# SCH_junwoo-board_2025-07-26.net
KiCad netlist of a schematic drawn in EasyEDA
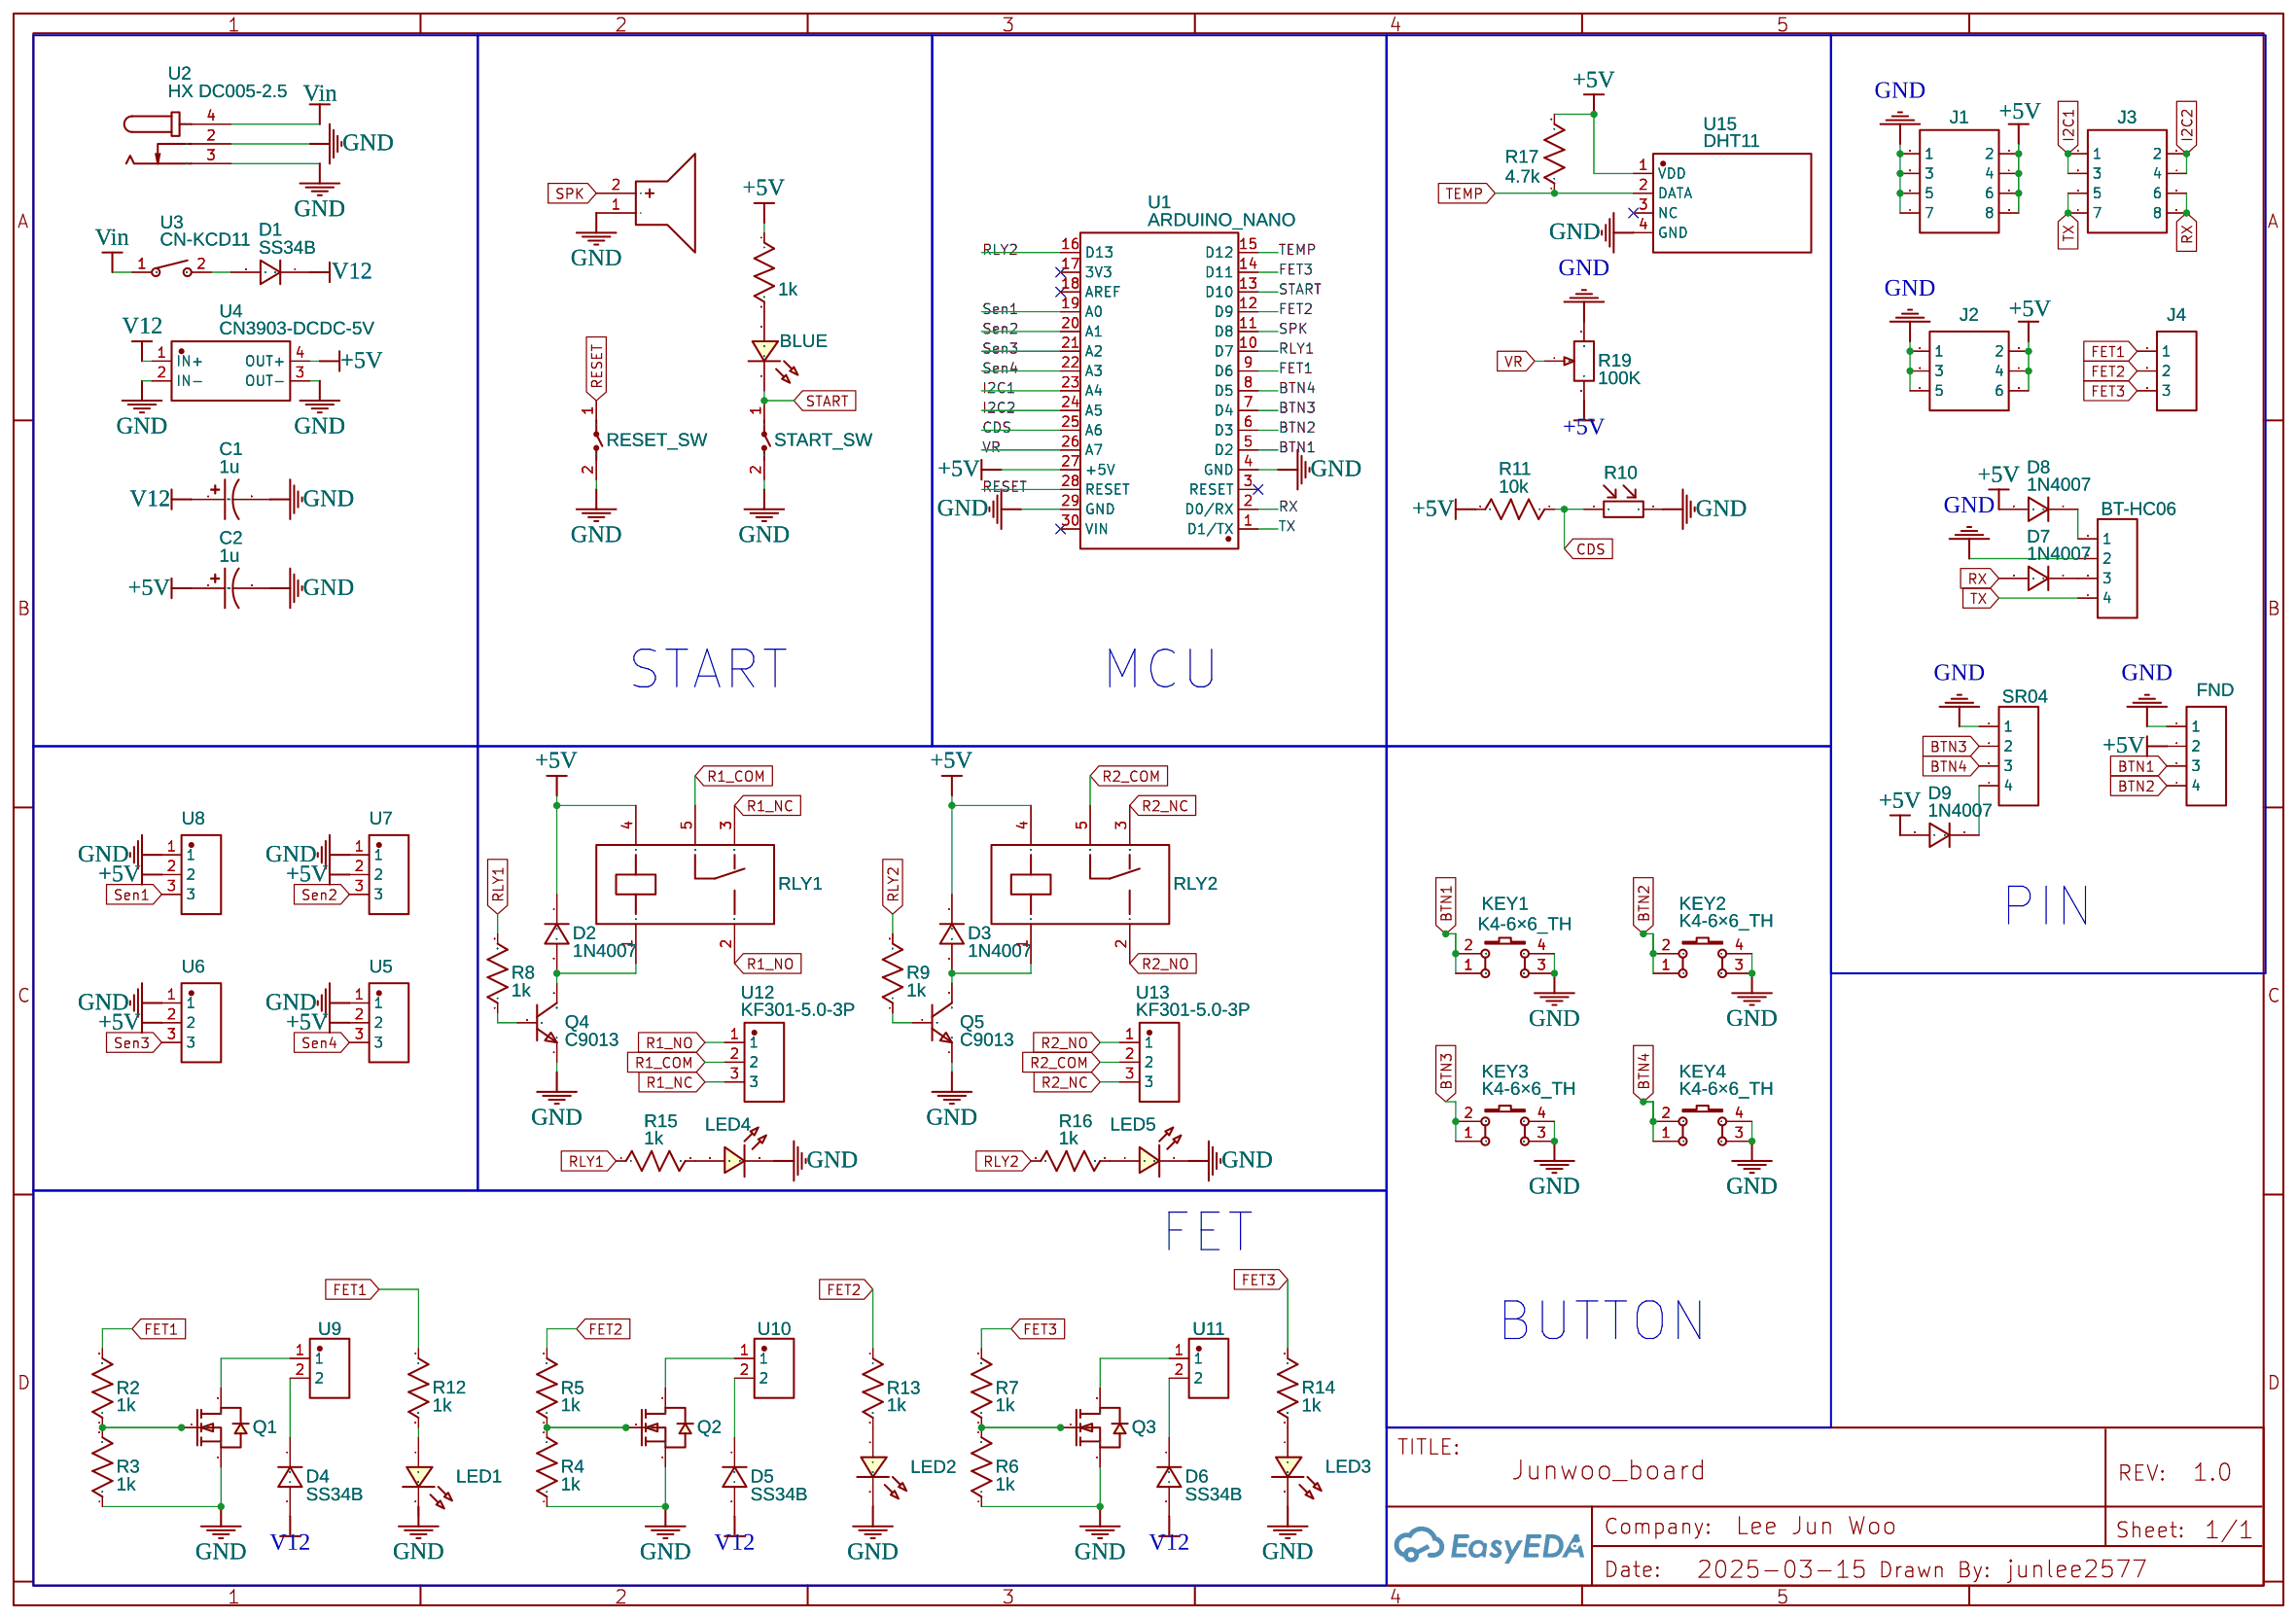
[diagram p0: schematic sheet]

(export (version "E")
  (design (tool "Eeschema 10.0.6"))
  (components
    (comp (ref "BLUE")
      (value "LED-TH-3mm_B")
      (fields
        (field (name "Manufacturer Part") "204-10SUBC/S400-A4")
        (field (name "Manufacturer") "EVERLIGHT(台湾亿光)")
      )
      (libsource (lib "") (part "LED-TH-3mm_B"))
    )
    (comp (ref "BT-HC06") (value "HDR-M-2.54_1x4") (libsource (lib "") (part "HDR-M-2.54_1x4_2")))
    (comp (ref "BUZZER1")
      (value "BUZZER")
      (fields (field (name "Manufacturer Part") "buzzer"))
      (libsource (lib "") (part "BUZZER"))
    )
    (comp (ref "C1") (value "1u") (libsource (lib "") (part "CE_TH_D6.3×F2.5_US")))
    (comp (ref "C2") (value "1u") (libsource (lib "") (part "CE_TH_D6.3×F2.5_US")))
    (comp (ref "D1")
      (value "SS34B")
      (fields (field (name "Manufacturer") "晶导微电子"))
      (libsource (lib "") (part "SS34B_1"))
    )
    (comp (ref "D2")
      (value "1N4007")
      (fields (field (name "Manufacturer") "SEMTECH"))
      (libsource (lib "") (part "1N4007_1"))
    )
    (comp (ref "D3")
      (value "1N4007")
      (fields (field (name "Manufacturer") "SEMTECH"))
      (libsource (lib "") (part "1N4007_1"))
    )
    (comp (ref "D4")
      (value "SS34B")
      (fields (field (name "Manufacturer") "晶导微电子"))
      (libsource (lib "") (part "SS34B"))
    )
    (comp (ref "D5")
      (value "SS34B")
      (fields (field (name "Manufacturer") "晶导微电子"))
      (libsource (lib "") (part "SS34B"))
    )
    (comp (ref "D6")
      (value "SS34B")
      (fields (field (name "Manufacturer") "晶导微电子"))
      (libsource (lib "") (part "SS34B"))
    )
    (comp (ref "D7")
      (value "1N4007")
      (fields (field (name "Manufacturer") "SEMTECH"))
      (libsource (lib "") (part "1N4007"))
    )
    (comp (ref "D8")
      (value "1N4007")
      (fields (field (name "Manufacturer") "SEMTECH"))
      (libsource (lib "") (part "1N4007"))
    )
    (comp (ref "D9")
      (value "1N4007")
      (fields (field (name "Manufacturer") "SEMTECH"))
      (libsource (lib "") (part "1N4007"))
    )
    (comp (ref "FND") (value "HDR-M-2.54_1x4") (libsource (lib "") (part "HDR-M-2.54_1x4")))
    (comp (ref "J1") (value "HDR-M-2.54_2x4") (libsource (lib "") (part "HDR-M-2.54_2x4")))
    (comp (ref "J2") (value "HDR-M-2.54_2x3") (libsource (lib "") (part "HDR-M-2.54_2x3")))
    (comp (ref "J3") (value "HDR-M-2.54_2x4") (libsource (lib "") (part "HDR-M-2.54_2x4")))
    (comp (ref "J4") (value "HDR-M-2.54_1x3") (libsource (lib "") (part "HDR-M-2.54_1x3")))
    (comp (ref "KEY1")
      (value "K4-6×6_TH")
      (fields (field (name "Manufacturer Part") "K2-1102DP-E4SW-04") (field (name "Manufacturer") "韩国韩荣"))
      (libsource (lib "") (part "K4-6×6_TH"))
    )
    (comp (ref "KEY2")
      (value "K4-6×6_TH")
      (fields (field (name "Manufacturer Part") "K2-1102DP-E4SW-04") (field (name "Manufacturer") "韩国韩荣"))
      (libsource (lib "") (part "K4-6×6_TH"))
    )
    (comp (ref "KEY3")
      (value "K4-6×6_TH")
      (fields (field (name "Manufacturer Part") "K2-1102DP-E4SW-04") (field (name "Manufacturer") "韩国韩荣"))
      (libsource (lib "") (part "K4-6×6_TH"))
    )
    (comp (ref "KEY4")
      (value "K4-6×6_TH")
      (fields (field (name "Manufacturer Part") "K2-1102DP-E4SW-04") (field (name "Manufacturer") "韩国韩荣"))
      (libsource (lib "") (part "K4-6×6_TH"))
    )
    (comp (ref "LED1") (value "LED-TH-5mm_B") (libsource (lib "") (part "LED-TH-5mm_B")))
    (comp (ref "LED2") (value "LED-TH-5mm_B") (libsource (lib "") (part "LED-TH-5mm_B")))
    (comp (ref "LED3") (value "LED-TH-5mm_B") (libsource (lib "") (part "LED-TH-5mm_B")))
    (comp (ref "LED4") (value "LED-TH-5mm_B") (libsource (lib "") (part "LED-TH-5mm_B_1")))
    (comp (ref "LED5") (value "LED-TH-5mm_B") (libsource (lib "") (part "LED-TH-5mm_B_1")))
    (comp (ref "Q1")
      (value "IRLZ44ZPBF")
      (fields (field (name "Manufacturer") "Infineon(英飞凌)"))
      (libsource (lib "") (part "IRLZ44ZPBF"))
    )
    (comp (ref "Q2")
      (value "IRLZ44ZPBF")
      (fields (field (name "Manufacturer") "Infineon(英飞凌)"))
      (libsource (lib "") (part "IRLZ44ZPBF"))
    )
    (comp (ref "Q3")
      (value "IRLZ44ZPBF")
      (fields (field (name "Manufacturer") "Infineon(英飞凌)"))
      (libsource (lib "") (part "IRLZ44ZPBF"))
    )
    (comp (ref "Q4") (value "C9013") (libsource (lib "") (part "C9013")))
    (comp (ref "Q5") (value "C9013") (libsource (lib "") (part "C9013")))
    (comp (ref "R1") (value "1k") (libsource (lib "") (part "R_AXIAL-0.4_US_2")))
    (comp (ref "R2") (value "1k") (libsource (lib "") (part "R_AXIAL-0.4_US_1")))
    (comp (ref "R3") (value "1k") (libsource (lib "") (part "R_AXIAL-0.4_US_1")))
    (comp (ref "R4") (value "1k") (libsource (lib "") (part "R_AXIAL-0.4_US_1")))
    (comp (ref "R5") (value "1k") (libsource (lib "") (part "R_AXIAL-0.4_US_1")))
    (comp (ref "R6") (value "1k") (libsource (lib "") (part "R_AXIAL-0.4_US_1")))
    (comp (ref "R7") (value "1k") (libsource (lib "") (part "R_AXIAL-0.4_US_1")))
    (comp (ref "R8") (value "1k") (libsource (lib "") (part "R_AXIAL-0.4_US_1")))
    (comp (ref "R9") (value "1k") (libsource (lib "") (part "R_AXIAL-0.4_US_1")))
    (comp (ref "R10")
      (value "GL5528(10-20)_C520869")
      (fields (field (name "Manufacturer Part") "GL5528(10-20)") (field (name "Manufacturer") "JCHL(晶创和立)"))
      (libsource (lib "") (part "GL5528(10-20)_C520869"))
    )
    (comp (ref "R11") (value "10k") (libsource (lib "") (part "R_AXIAL-0.4_US_3")))
    (comp (ref "R12") (value "1k") (libsource (lib "") (part "R_AXIAL-0.4_US_2")))
    (comp (ref "R13") (value "1k") (libsource (lib "") (part "R_AXIAL-0.4_US_2")))
    (comp (ref "R14") (value "1k") (libsource (lib "") (part "R_AXIAL-0.4_US_2")))
    (comp (ref "R15") (value "1k") (libsource (lib "") (part "R_AXIAL-0.4_US")))
    (comp (ref "R16") (value "1k") (libsource (lib "") (part "R_AXIAL-0.4_US")))
    (comp (ref "R17") (value "4.7k") (libsource (lib "") (part "R_AXIAL-0.4_US_1")))
    (comp (ref "R19")
      (value "100K")
      (fields
        (field (name "Manufacturer Part") "Potentiometer WH160-1-104")
        (field (name "Manufacturer") "JML")
      )
      (libsource (lib "") (part "RV09AF_schütze"))
    )
    (comp (ref "RESET_SW")
      (value "TS-1001-AR04326")
      (fields (field (name "Manufacturer") "XUNPU(讯普)"))
      (libsource (lib "") (part "TS-1001-AR04326_1"))
    )
    (comp (ref "RLY1")
      (value "5V-12V SRD05VDCSLC")
      (fields (field (name "Manufacturer Part") "SRD-05VDC-SL-C") (field (name "Manufacturer") "松乐"))
      (libsource (lib "") (part "SRD-05VDC-SL-C"))
    )
    (comp (ref "RLY2")
      (value "5V-12V SRD05VDCSLC")
      (fields (field (name "Manufacturer Part") "SRD-05VDC-SL-C") (field (name "Manufacturer") "松乐"))
      (libsource (lib "") (part "SRD-05VDC-SL-C"))
    )
    (comp (ref "SR04") (value "HDR-M-2.54_1x4") (libsource (lib "") (part "HDR-M-2.54_1x4_1")))
    (comp (ref "START_SW")
      (value "TS-1001-AR04326")
      (fields (field (name "Manufacturer") "XUNPU(讯普)"))
      (libsource (lib "") (part "TS-1001-AR04326"))
    )
    (comp (ref "U1") (value "ARDUINO_NANO") (libsource (lib "") (part "ARDUINO_NANO")))
    (comp (ref "U2")
      (value "HX DC005-2.5")
      (fields (field (name "Manufacturer") "hanxia(韩下)"))
      (libsource (lib "") (part "HX DC005-2.5"))
    )
    (comp (ref "U3") (value "CN-KCD11") (libsource (lib "") (part "CN-KCD11")))
    (comp (ref "U4") (value "CN3903-DCDC-5V") (libsource (lib "") (part "CN3903-DCDC-STEPDOWN-5V")))
    (comp (ref "U5")
      (value "KF350-3.5-3P")
      (fields (field (name "Manufacturer") "KEFA(科发)"))
      (libsource (lib "") (part "KF350-3.5-3P"))
    )
    (comp (ref "U6")
      (value "KF350-3.5-3P")
      (fields (field (name "Manufacturer") "KEFA(科发)"))
      (libsource (lib "") (part "KF350-3.5-3P"))
    )
    (comp (ref "U7")
      (value "KF350-3.5-3P")
      (fields (field (name "Manufacturer") "KEFA(科发)"))
      (libsource (lib "") (part "KF350-3.5-3P"))
    )
    (comp (ref "U8")
      (value "KF350-3.5-3P")
      (fields (field (name "Manufacturer") "KEFA(科发)"))
      (libsource (lib "") (part "KF350-3.5-3P"))
    )
    (comp (ref "U9")
      (value "KF301-5.0-2P")
      (fields (field (name "Manufacturer") "KEFA(科发)"))
      (libsource (lib "") (part "KF301-5.0-2P"))
    )
    (comp (ref "U10")
      (value "KF301-5.0-2P")
      (fields (field (name "Manufacturer") "KEFA(科发)"))
      (libsource (lib "") (part "KF301-5.0-2P"))
    )
    (comp (ref "U11")
      (value "KF301-5.0-2P")
      (fields (field (name "Manufacturer") "KEFA(科发)"))
      (libsource (lib "") (part "KF301-5.0-2P"))
    )
    (comp (ref "U12")
      (value "KF301-5.0-3P")
      (fields (field (name "Manufacturer") "KEFA(科发)"))
      (libsource (lib "") (part "KF301-5.0-3P"))
    )
    (comp (ref "U13")
      (value "KF301-5.0-3P")
      (fields (field (name "Manufacturer") "KEFA(科发)"))
      (libsource (lib "") (part "KF301-5.0-3P"))
    )
    (comp (ref "U15")
      (value "DHT11")
      (fields (field (name "Manufacturer") "广州奥松"))
      (libsource (lib "") (part "DHT11"))
    )
  )
  (nets
    (net (code "1") (name "+5V") (class "Default")
      (node (ref "C2") (pin "1") (pinfunction "1_1") (pintype "unspecified"))
      (node (ref "D2") (pin "1") (pinfunction "1_1") (pintype "unspecified"))
      (node (ref "D3") (pin "1") (pinfunction "1_1") (pintype "unspecified"))
      (node (ref "D8") (pin "2") (pinfunction "2_2") (pintype "unspecified"))
      (node (ref "D9") (pin "2") (pinfunction "2_2") (pintype "unspecified"))
      (node (ref "FND") (pin "2") (pinfunction "2_2") (pintype "unspecified"))
      (node (ref "J1") (pin "2") (pinfunction "2_2") (pintype "unspecified"))
      (node (ref "J1") (pin "4") (pinfunction "4_4") (pintype "unspecified"))
      (node (ref "J1") (pin "6") (pinfunction "6_6") (pintype "unspecified"))
      (node (ref "J1") (pin "8") (pinfunction "8_8") (pintype "unspecified"))
      (node (ref "J2") (pin "2") (pinfunction "2_2") (pintype "input"))
      (node (ref "J2") (pin "4") (pinfunction "4_4") (pintype "input"))
      (node (ref "J2") (pin "6") (pinfunction "6_6") (pintype "input"))
      (node (ref "R1") (pin "1") (pinfunction "1_1") (pintype "unspecified"))
      (node (ref "R11") (pin "2") (pinfunction "2_2") (pintype "unspecified"))
      (node (ref "R17") (pin "2") (pinfunction "2_2") (pintype "unspecified"))
      (node (ref "R19") (pin "3") (pinfunction "1_3") (pintype "input"))
      (node (ref "RLY1") (pin "4") (pinfunction "4_4") (pintype "unspecified"))
      (node (ref "RLY2") (pin "4") (pinfunction "4_4") (pintype "unspecified"))
      (node (ref "U1") (pin "27") (pinfunction "+5V_27") (pintype "unspecified"))
      (node (ref "U15") (pin "1") (pinfunction "VDD_1") (pintype "unspecified"))
      (node (ref "U4") (pin "4") (pinfunction "OUT+_4") (pintype "unspecified"))
      (node (ref "U5") (pin "2") (pinfunction "2_2") (pintype "unspecified"))
      (node (ref "U6") (pin "2") (pinfunction "2_2") (pintype "unspecified"))
      (node (ref "U7") (pin "2") (pinfunction "2_2") (pintype "unspecified"))
      (node (ref "U8") (pin "2") (pinfunction "2_2") (pintype "unspecified"))
    )
    (net (code "2") (name "BTN1") (class "Default")
      (node (ref "FND") (pin "3") (pinfunction "3_3") (pintype "unspecified"))
      (node (ref "KEY1") (pin "1") (pinfunction "1_1") (pintype "unspecified"))
      (node (ref "KEY1") (pin "2") (pinfunction "2_2") (pintype "unspecified"))
      (node (ref "U1") (pin "5") (pinfunction "D2_5") (pintype "unspecified"))
    )
    (net (code "3") (name "BTN2") (class "Default")
      (node (ref "FND") (pin "4") (pinfunction "4_4") (pintype "unspecified"))
      (node (ref "KEY2") (pin "1") (pinfunction "1_1") (pintype "unspecified"))
      (node (ref "KEY2") (pin "2") (pinfunction "2_2") (pintype "unspecified"))
      (node (ref "U1") (pin "6") (pinfunction "D3_6") (pintype "unspecified"))
    )
    (net (code "4") (name "BTN3") (class "Default")
      (node (ref "KEY3") (pin "1") (pinfunction "1_1") (pintype "unspecified"))
      (node (ref "KEY3") (pin "2") (pinfunction "2_2") (pintype "unspecified"))
      (node (ref "SR04") (pin "2") (pinfunction "2_2") (pintype "unspecified"))
      (node (ref "U1") (pin "7") (pinfunction "D4_7") (pintype "unspecified"))
    )
    (net (code "5") (name "BTN4") (class "Default")
      (node (ref "KEY4") (pin "1") (pinfunction "1_1") (pintype "unspecified"))
      (node (ref "KEY4") (pin "2") (pinfunction "2_2") (pintype "unspecified"))
      (node (ref "SR04") (pin "3") (pinfunction "3_3") (pintype "unspecified"))
      (node (ref "U1") (pin "8") (pinfunction "D5_8") (pintype "unspecified"))
    )
    (net (code "6") (name "CDS") (class "Default")
      (node (ref "R10") (pin "1") (pinfunction "1_1") (pintype "input"))
      (node (ref "R11") (pin "1") (pinfunction "1_1") (pintype "unspecified"))
      (node (ref "U1") (pin "25") (pinfunction "A6_25") (pintype "unspecified"))
    )
    (net (code "7") (name "FET1") (class "Default")
      (node (ref "J4") (pin "1") (pinfunction "1_1") (pintype "input"))
      (node (ref "R12") (pin "1") (pinfunction "1_1") (pintype "unspecified"))
      (node (ref "R2") (pin "2") (pinfunction "2_2") (pintype "unspecified"))
      (node (ref "U1") (pin "9") (pinfunction "D6_9") (pintype "unspecified"))
    )
    (net (code "8") (name "FET2") (class "Default")
      (node (ref "J4") (pin "2") (pinfunction "2_2") (pintype "input"))
      (node (ref "R13") (pin "1") (pinfunction "1_1") (pintype "unspecified"))
      (node (ref "R5") (pin "2") (pinfunction "2_2") (pintype "unspecified"))
      (node (ref "U1") (pin "12") (pinfunction "D9_12") (pintype "unspecified"))
    )
    (net (code "9") (name "FET3") (class "Default")
      (node (ref "J4") (pin "3") (pinfunction "3_3") (pintype "input"))
      (node (ref "R14") (pin "1") (pinfunction "1_1") (pintype "unspecified"))
      (node (ref "R7") (pin "2") (pinfunction "2_2") (pintype "unspecified"))
      (node (ref "U1") (pin "14") (pinfunction "D11_14") (pintype "unspecified"))
    )
    (net (code "10") (name "GND") (class "Default")
      (node (ref "BT-HC06") (pin "2") (pinfunction "2_2") (pintype "unspecified"))
      (node (ref "BUZZER1") (pin "1") (pinfunction "-_1") (pintype "unspecified"))
      (node (ref "C1") (pin "2") (pinfunction "2_2") (pintype "unspecified"))
      (node (ref "C2") (pin "2") (pinfunction "2_2") (pintype "unspecified"))
      (node (ref "FND") (pin "1") (pinfunction "1_1") (pintype "unspecified"))
      (node (ref "J1") (pin "1") (pinfunction "1_1") (pintype "unspecified"))
      (node (ref "J1") (pin "3") (pinfunction "3_3") (pintype "unspecified"))
      (node (ref "J1") (pin "5") (pinfunction "5_5") (pintype "unspecified"))
      (node (ref "J1") (pin "7") (pinfunction "7_7") (pintype "unspecified"))
      (node (ref "J2") (pin "1") (pinfunction "1_1") (pintype "input"))
      (node (ref "J2") (pin "3") (pinfunction "3_3") (pintype "input"))
      (node (ref "J2") (pin "5") (pinfunction "5_5") (pintype "input"))
      (node (ref "KEY1") (pin "3") (pinfunction "3_3") (pintype "unspecified"))
      (node (ref "KEY1") (pin "4") (pinfunction "4_4") (pintype "unspecified"))
      (node (ref "KEY2") (pin "3") (pinfunction "3_3") (pintype "unspecified"))
      (node (ref "KEY2") (pin "4") (pinfunction "4_4") (pintype "unspecified"))
      (node (ref "KEY3") (pin "3") (pinfunction "3_3") (pintype "unspecified"))
      (node (ref "KEY3") (pin "4") (pinfunction "4_4") (pintype "unspecified"))
      (node (ref "KEY4") (pin "3") (pinfunction "3_3") (pintype "unspecified"))
      (node (ref "KEY4") (pin "4") (pinfunction "4_4") (pintype "unspecified"))
      (node (ref "LED1") (pin "2") (pinfunction "2_2") (pintype "unspecified"))
      (node (ref "LED2") (pin "2") (pinfunction "2_2") (pintype "unspecified"))
      (node (ref "LED3") (pin "2") (pinfunction "2_2") (pintype "unspecified"))
      (node (ref "LED4") (pin "2") (pinfunction "2_2") (pintype "unspecified"))
      (node (ref "LED5") (pin "2") (pinfunction "2_2") (pintype "unspecified"))
      (node (ref "Q1") (pin "3") (pinfunction "S_3") (pintype "unspecified"))
      (node (ref "Q2") (pin "3") (pinfunction "S_3") (pintype "unspecified"))
      (node (ref "Q3") (pin "3") (pinfunction "S_3") (pintype "unspecified"))
      (node (ref "Q4") (pin "1") (pinfunction "E_1") (pintype "unspecified"))
      (node (ref "Q5") (pin "1") (pinfunction "E_1") (pintype "unspecified"))
      (node (ref "R10") (pin "2") (pinfunction "2_2") (pintype "input"))
      (node (ref "R19") (pin "2") (pinfunction "3_2") (pintype "input"))
      (node (ref "R3") (pin "1") (pinfunction "1_1") (pintype "unspecified"))
      (node (ref "R4") (pin "1") (pinfunction "1_1") (pintype "unspecified"))
      (node (ref "R6") (pin "1") (pinfunction "1_1") (pintype "unspecified"))
      (node (ref "RESET_SW") (pin "2") (pinfunction "2_2") (pintype "unspecified"))
      (node (ref "SR04") (pin "1") (pinfunction "1_1") (pintype "unspecified"))
      (node (ref "START_SW") (pin "2") (pinfunction "2_2") (pintype "unspecified"))
      (node (ref "U1") (pin "29") (pinfunction "GND_29") (pintype "unspecified"))
      (node (ref "U1") (pin "4") (pinfunction "GND_4") (pintype "unspecified"))
      (node (ref "U15") (pin "4") (pinfunction "GND_4") (pintype "unspecified"))
      (node (ref "U2") (pin "2") (pinfunction "2_2") (pintype "unspecified"))
      (node (ref "U2") (pin "3") (pinfunction "3_3") (pintype "unspecified"))
      (node (ref "U4") (pin "2") (pinfunction "IN-_2") (pintype "unspecified"))
      (node (ref "U4") (pin "3") (pinfunction "OUT-_3") (pintype "unspecified"))
      (node (ref "U5") (pin "1") (pinfunction "1_1") (pintype "unspecified"))
      (node (ref "U6") (pin "1") (pinfunction "1_1") (pintype "unspecified"))
      (node (ref "U7") (pin "1") (pinfunction "1_1") (pintype "unspecified"))
      (node (ref "U8") (pin "1") (pinfunction "1_1") (pintype "unspecified"))
    )
    (net (code "11") (name "I2C1") (class "Default")
      (node (ref "J3") (pin "1") (pinfunction "1_1") (pintype "unspecified"))
      (node (ref "J3") (pin "3") (pinfunction "3_3") (pintype "unspecified"))
      (node (ref "U1") (pin "23") (pinfunction "A4_23") (pintype "unspecified"))
    )
    (net (code "12") (name "I2C2") (class "Default")
      (node (ref "J3") (pin "2") (pinfunction "2_2") (pintype "unspecified"))
      (node (ref "J3") (pin "4") (pinfunction "4_4") (pintype "unspecified"))
      (node (ref "U1") (pin "24") (pinfunction "A5_24") (pintype "unspecified"))
    )
    (net (code "13") (name "Net-(BLUE-Pad1)") (class "Default")
      (node (ref "BLUE") (pin "1") (pinfunction "1_1") (pintype "unspecified"))
      (node (ref "R1") (pin "2") (pinfunction "2_2") (pintype "unspecified"))
    )
    (net (code "14") (name "Net-(BT-HC06-Pad1)") (class "Default")
      (node (ref "BT-HC06") (pin "1") (pinfunction "1_1") (pintype "unspecified"))
      (node (ref "D8") (pin "1") (pinfunction "1_1") (pintype "unspecified"))
    )
    (net (code "15") (name "Net-(BT-HC06-Pad3)") (class "Default")
      (node (ref "BT-HC06") (pin "3") (pinfunction "3_3") (pintype "unspecified"))
      (node (ref "D7") (pin "1") (pinfunction "1_1") (pintype "unspecified"))
    )
    (net (code "16") (name "Net-(D1-A)") (class "Default")
      (node (ref "D1") (pin "2") (pinfunction "A_2") (pintype "unspecified"))
      (node (ref "U3") (pin "2") (pinfunction "2_2") (pintype "unspecified"))
    )
    (net (code "17") (name "Net-(D4-C)") (class "Default")
      (node (ref "D4") (pin "1") (pinfunction "C_1") (pintype "unspecified"))
      (node (ref "U9") (pin "2") (pinfunction "2_2") (pintype "unspecified"))
    )
    (net (code "18") (name "Net-(D5-C)") (class "Default")
      (node (ref "D5") (pin "1") (pinfunction "C_1") (pintype "unspecified"))
      (node (ref "U10") (pin "2") (pinfunction "2_2") (pintype "unspecified"))
    )
    (net (code "19") (name "Net-(D6-C)") (class "Default")
      (node (ref "D6") (pin "1") (pinfunction "C_1") (pintype "unspecified"))
      (node (ref "U11") (pin "2") (pinfunction "2_2") (pintype "unspecified"))
    )
    (net (code "20") (name "Net-(D9-Pad1)") (class "Default")
      (node (ref "D9") (pin "1") (pinfunction "1_1") (pintype "unspecified"))
      (node (ref "SR04") (pin "4") (pinfunction "4_4") (pintype "unspecified"))
    )
    (net (code "21") (name "Net-(LED1-Pad1)") (class "Default")
      (node (ref "LED1") (pin "1") (pinfunction "1_1") (pintype "unspecified"))
      (node (ref "R12") (pin "2") (pinfunction "2_2") (pintype "unspecified"))
    )
    (net (code "22") (name "Net-(LED2-Pad1)") (class "Default")
      (node (ref "LED2") (pin "1") (pinfunction "1_1") (pintype "unspecified"))
      (node (ref "R13") (pin "2") (pinfunction "2_2") (pintype "unspecified"))
    )
    (net (code "23") (name "Net-(LED3-Pad1)") (class "Default")
      (node (ref "LED3") (pin "1") (pinfunction "1_1") (pintype "unspecified"))
      (node (ref "R14") (pin "2") (pinfunction "2_2") (pintype "unspecified"))
    )
    (net (code "24") (name "Net-(LED4-Pad1)") (class "Default")
      (node (ref "LED4") (pin "1") (pinfunction "1_1") (pintype "unspecified"))
      (node (ref "R15") (pin "2") (pinfunction "2_2") (pintype "unspecified"))
    )
    (net (code "25") (name "Net-(LED5-Pad1)") (class "Default")
      (node (ref "LED5") (pin "1") (pinfunction "1_1") (pintype "unspecified"))
      (node (ref "R16") (pin "2") (pinfunction "2_2") (pintype "unspecified"))
    )
    (net (code "26") (name "Net-(Q1-D)") (class "Default")
      (node (ref "Q1") (pin "2") (pinfunction "D_2") (pintype "unspecified"))
      (node (ref "U9") (pin "1") (pinfunction "1_1") (pintype "unspecified"))
    )
    (net (code "27") (name "Net-(Q1-G)") (class "Default")
      (node (ref "Q1") (pin "1") (pinfunction "G_1") (pintype "unspecified"))
      (node (ref "R2") (pin "1") (pinfunction "1_1") (pintype "unspecified"))
      (node (ref "R3") (pin "2") (pinfunction "2_2") (pintype "unspecified"))
    )
    (net (code "28") (name "Net-(Q2-D)") (class "Default")
      (node (ref "Q2") (pin "2") (pinfunction "D_2") (pintype "unspecified"))
      (node (ref "U10") (pin "1") (pinfunction "1_1") (pintype "unspecified"))
    )
    (net (code "29") (name "Net-(Q2-G)") (class "Default")
      (node (ref "Q2") (pin "1") (pinfunction "G_1") (pintype "unspecified"))
      (node (ref "R4") (pin "2") (pinfunction "2_2") (pintype "unspecified"))
      (node (ref "R5") (pin "1") (pinfunction "1_1") (pintype "unspecified"))
    )
    (net (code "30") (name "Net-(Q3-D)") (class "Default")
      (node (ref "Q3") (pin "2") (pinfunction "D_2") (pintype "unspecified"))
      (node (ref "U11") (pin "1") (pinfunction "1_1") (pintype "unspecified"))
    )
    (net (code "31") (name "Net-(Q3-G)") (class "Default")
      (node (ref "Q3") (pin "1") (pinfunction "G_1") (pintype "unspecified"))
      (node (ref "R6") (pin "2") (pinfunction "2_2") (pintype "unspecified"))
      (node (ref "R7") (pin "1") (pinfunction "1_1") (pintype "unspecified"))
    )
    (net (code "32") (name "Net-(Q4-B)") (class "Default")
      (node (ref "Q4") (pin "2") (pinfunction "B_2") (pintype "unspecified"))
      (node (ref "R8") (pin "1") (pinfunction "1_1") (pintype "unspecified"))
    )
    (net (code "33") (name "Net-(Q4-C)") (class "Default")
      (node (ref "D2") (pin "2") (pinfunction "2_2") (pintype "unspecified"))
      (node (ref "Q4") (pin "3") (pinfunction "C_3") (pintype "unspecified"))
      (node (ref "RLY1") (pin "1") (pinfunction "1_1") (pintype "unspecified"))
    )
    (net (code "34") (name "Net-(Q5-B)") (class "Default")
      (node (ref "Q5") (pin "2") (pinfunction "B_2") (pintype "unspecified"))
      (node (ref "R9") (pin "1") (pinfunction "1_1") (pintype "unspecified"))
    )
    (net (code "35") (name "Net-(Q5-C)") (class "Default")
      (node (ref "D3") (pin "2") (pinfunction "2_2") (pintype "unspecified"))
      (node (ref "Q5") (pin "3") (pinfunction "C_3") (pintype "unspecified"))
      (node (ref "RLY2") (pin "1") (pinfunction "1_1") (pintype "unspecified"))
    )
    (net (code "36") (name "R1_COM") (class "Default")
      (node (ref "RLY1") (pin "5") (pinfunction "5_5") (pintype "unspecified"))
      (node (ref "U12") (pin "2") (pinfunction "2_2") (pintype "unspecified"))
    )
    (net (code "37") (name "R1_NC") (class "Default")
      (node (ref "RLY1") (pin "3") (pinfunction "3_3") (pintype "unspecified"))
      (node (ref "U12") (pin "3") (pinfunction "3_3") (pintype "unspecified"))
    )
    (net (code "38") (name "R1_NO") (class "Default")
      (node (ref "RLY1") (pin "2") (pinfunction "2_2") (pintype "unspecified"))
      (node (ref "U12") (pin "1") (pinfunction "1_1") (pintype "unspecified"))
    )
    (net (code "39") (name "R2_COM") (class "Default")
      (node (ref "RLY2") (pin "5") (pinfunction "5_5") (pintype "unspecified"))
      (node (ref "U13") (pin "2") (pinfunction "2_2") (pintype "unspecified"))
    )
    (net (code "40") (name "R2_NC") (class "Default")
      (node (ref "RLY2") (pin "3") (pinfunction "3_3") (pintype "unspecified"))
      (node (ref "U13") (pin "3") (pinfunction "3_3") (pintype "unspecified"))
    )
    (net (code "41") (name "R2_NO") (class "Default")
      (node (ref "RLY2") (pin "2") (pinfunction "2_2") (pintype "unspecified"))
      (node (ref "U13") (pin "1") (pinfunction "1_1") (pintype "unspecified"))
    )
    (net (code "42") (name "RESET") (class "Default")
      (node (ref "RESET_SW") (pin "1") (pinfunction "1_1") (pintype "unspecified"))
      (node (ref "U1") (pin "28") (pinfunction "RESET_28") (pintype "unspecified"))
    )
    (net (code "43") (name "RLY1") (class "Default")
      (node (ref "R15") (pin "1") (pinfunction "1_1") (pintype "unspecified"))
      (node (ref "R8") (pin "2") (pinfunction "2_2") (pintype "unspecified"))
      (node (ref "U1") (pin "10") (pinfunction "D7_10") (pintype "unspecified"))
    )
    (net (code "44") (name "RLY2") (class "Default")
      (node (ref "R16") (pin "1") (pinfunction "1_1") (pintype "unspecified"))
      (node (ref "R9") (pin "2") (pinfunction "2_2") (pintype "unspecified"))
      (node (ref "U1") (pin "16") (pinfunction "D13_16") (pintype "unspecified"))
    )
    (net (code "45") (name "RX") (class "Default")
      (node (ref "D7") (pin "2") (pinfunction "2_2") (pintype "unspecified"))
      (node (ref "J3") (pin "6") (pinfunction "6_6") (pintype "unspecified"))
      (node (ref "J3") (pin "8") (pinfunction "8_8") (pintype "unspecified"))
      (node (ref "U1") (pin "2") (pinfunction "D0/RX_2") (pintype "unspecified"))
    )
    (net (code "46") (name "SPK") (class "Default")
      (node (ref "BUZZER1") (pin "2") (pinfunction "+_2") (pintype "unspecified"))
      (node (ref "U1") (pin "11") (pinfunction "D8_11") (pintype "unspecified"))
    )
    (net (code "47") (name "START") (class "Default")
      (node (ref "BLUE") (pin "2") (pinfunction "2_2") (pintype "unspecified"))
      (node (ref "START_SW") (pin "1") (pinfunction "1_1") (pintype "unspecified"))
      (node (ref "U1") (pin "13") (pinfunction "D10_13") (pintype "unspecified"))
    )
    (net (code "48") (name "Sen1") (class "Default")
      (node (ref "U1") (pin "19") (pinfunction "A0_19") (pintype "unspecified"))
      (node (ref "U8") (pin "3") (pinfunction "3_3") (pintype "unspecified"))
    )
    (net (code "49") (name "Sen2") (class "Default")
      (node (ref "U1") (pin "20") (pinfunction "A1_20") (pintype "unspecified"))
      (node (ref "U7") (pin "3") (pinfunction "3_3") (pintype "unspecified"))
    )
    (net (code "50") (name "Sen3") (class "Default")
      (node (ref "U1") (pin "21") (pinfunction "A2_21") (pintype "unspecified"))
      (node (ref "U6") (pin "3") (pinfunction "3_3") (pintype "unspecified"))
    )
    (net (code "51") (name "Sen4") (class "Default")
      (node (ref "U1") (pin "22") (pinfunction "A3_22") (pintype "unspecified"))
      (node (ref "U5") (pin "3") (pinfunction "3_3") (pintype "unspecified"))
    )
    (net (code "52") (name "TEMP") (class "Default")
      (node (ref "R17") (pin "1") (pinfunction "1_1") (pintype "unspecified"))
      (node (ref "U1") (pin "15") (pinfunction "D12_15") (pintype "unspecified"))
      (node (ref "U15") (pin "2") (pinfunction "DATA_2") (pintype "unspecified"))
    )
    (net (code "53") (name "TX") (class "Default")
      (node (ref "BT-HC06") (pin "4") (pinfunction "4_4") (pintype "unspecified"))
      (node (ref "J3") (pin "5") (pinfunction "5_5") (pintype "unspecified"))
      (node (ref "J3") (pin "7") (pinfunction "7_7") (pintype "unspecified"))
      (node (ref "U1") (pin "1") (pinfunction "D1/TX_1") (pintype "unspecified"))
    )
    (net (code "54") (name "V12") (class "Default")
      (node (ref "C1") (pin "1") (pinfunction "1_1") (pintype "unspecified"))
      (node (ref "D1") (pin "1") (pinfunction "C_1") (pintype "unspecified"))
      (node (ref "D4") (pin "2") (pinfunction "A_2") (pintype "unspecified"))
      (node (ref "D5") (pin "2") (pinfunction "A_2") (pintype "unspecified"))
      (node (ref "D6") (pin "2") (pinfunction "A_2") (pintype "unspecified"))
      (node (ref "U4") (pin "1") (pinfunction "IN+_1") (pintype "unspecified"))
    )
    (net (code "55") (name "VR") (class "Default")
      (node (ref "R19") (pin "1") (pinfunction "2_1") (pintype "input"))
      (node (ref "U1") (pin "26") (pinfunction "A7_26") (pintype "unspecified"))
    )
    (net (code "56") (name "Vin") (class "Default")
      (node (ref "U2") (pin "4") (pinfunction "4_4") (pintype "unspecified"))
      (node (ref "U3") (pin "1") (pinfunction "1_1") (pintype "unspecified"))
    )
    (net (code "57") (name "unconnected-(U1-3V3-Pad17)") (class "Default")
      (node (ref "U1") (pin "17") (pinfunction "3V3_17") (pintype "unspecified+no_connect"))
    )
    (net (code "58") (name "unconnected-(U1-AREF-Pad18)") (class "Default")
      (node (ref "U1") (pin "18") (pinfunction "AREF_18") (pintype "unspecified+no_connect"))
    )
    (net (code "59") (name "unconnected-(U1-RESET-Pad3)") (class "Default")
      (node (ref "U1") (pin "3") (pinfunction "RESET_3") (pintype "unspecified+no_connect"))
    )
    (net (code "60") (name "unconnected-(U1-VIN-Pad30)") (class "Default")
      (node (ref "U1") (pin "30") (pinfunction "VIN_30") (pintype "unspecified+no_connect"))
    )
    (net (code "61") (name "unconnected-(U15-NC-Pad3)") (class "Default")
      (node (ref "U15") (pin "3") (pinfunction "NC_3") (pintype "unspecified+no_connect"))
    )
  )
)
